# Project_design_v1_0.net
KiCad netlist of a schematic drawn in EAGLE
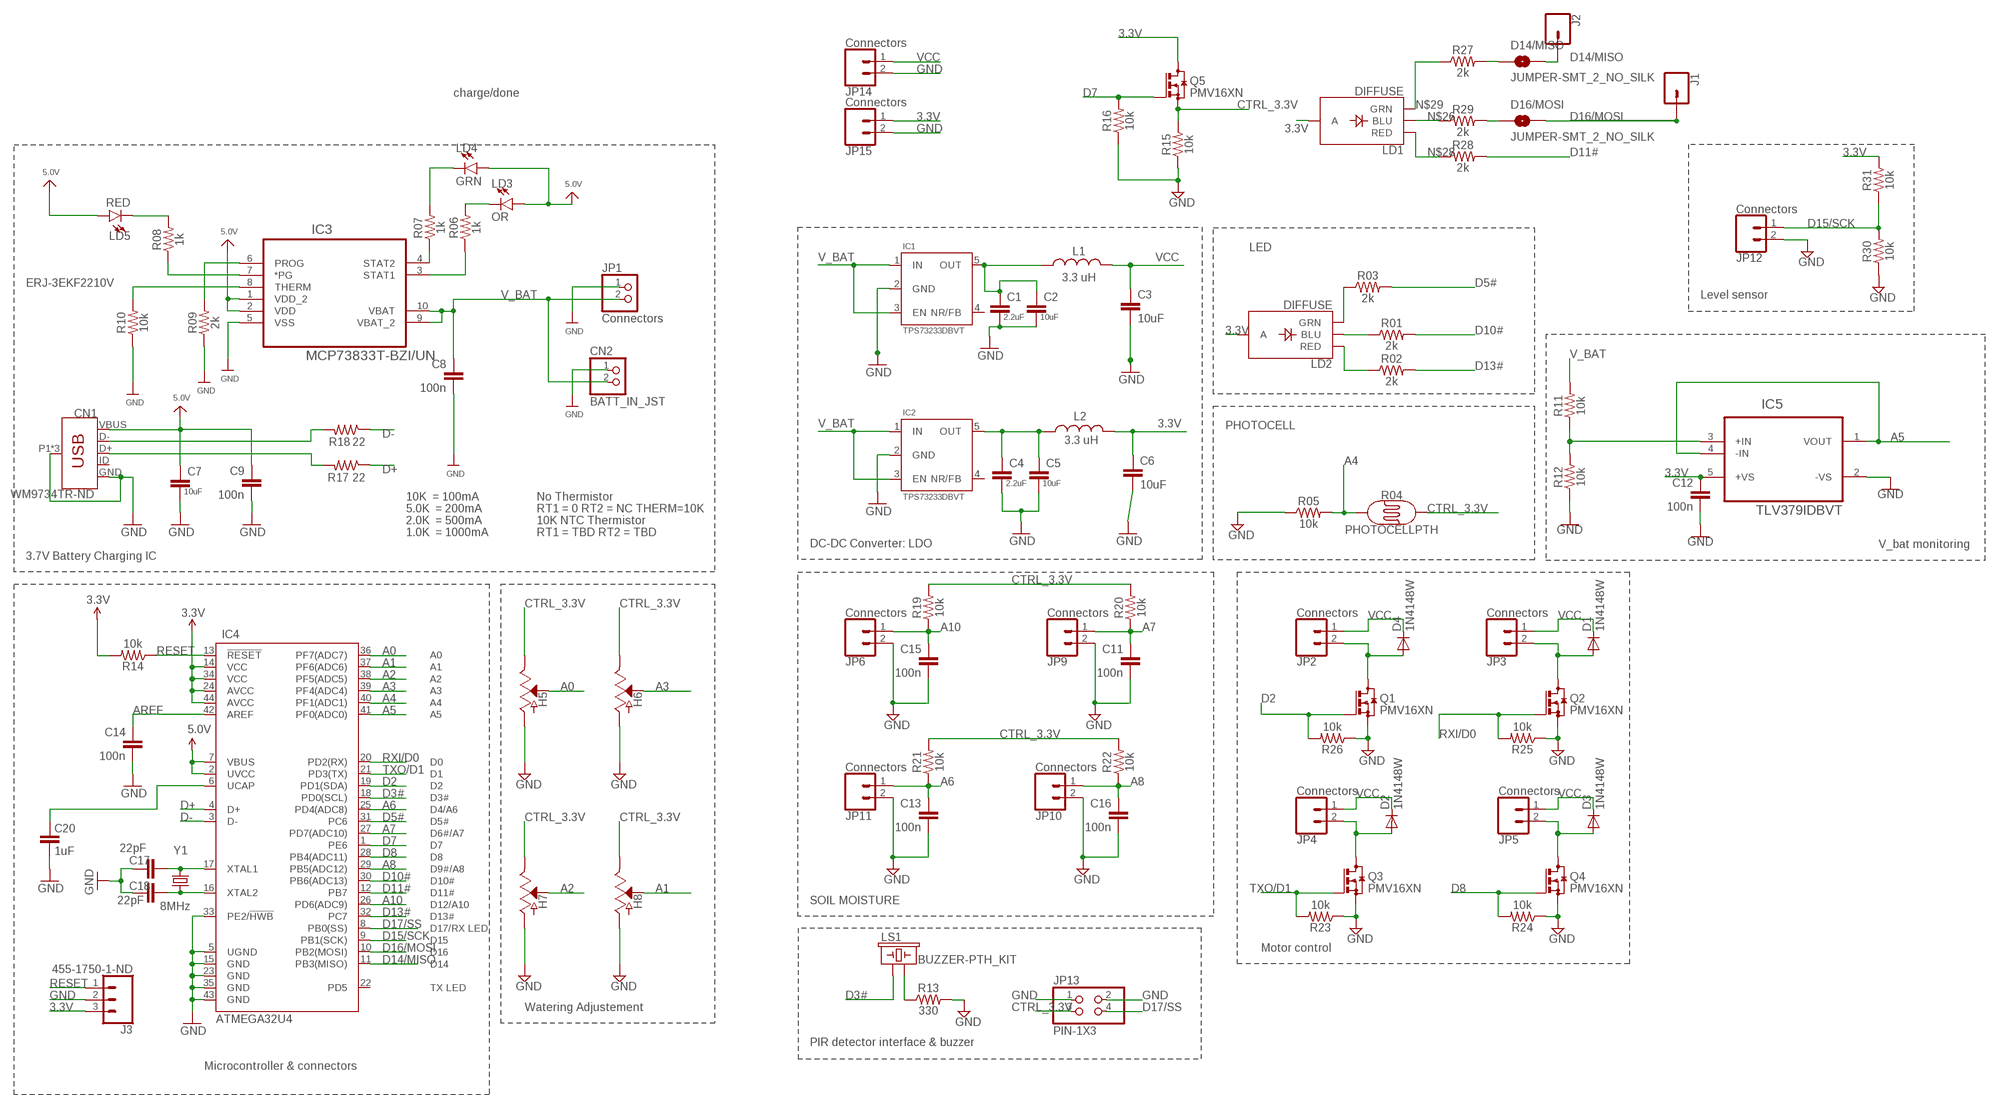
[diagram p0: schematic, sheet 1]

(export (version "E")
  (design (tool "Eeschema 10.0.6"))
  (components
    (comp (ref "C1")
      (value "2.2uF")
      (footprint "eagle-import:0603-CAP")
      (fields (field (name "PARTNO") "C1608X7S1C225K080AC"))
      (libsource (lib "eagle-import") (part "SparkFun-Passives_CAP0603-CAP"))
    )
    (comp (ref "C2")
      (value "10uF")
      (footprint "eagle-import:0603-CAP")
      (fields (field (name "PARTNO") "GRM188R60J106ME47D"))
      (libsource (lib "eagle-import") (part "SparkFun-Passives_CAP0603-CAP"))
    )
    (comp (ref "C3")
      (value "10uF")
      (footprint "eagle-import:0603-CAP")
      (fields (field (name "PARTNO") "GRM188R60J106ME47D"))
      (libsource (lib "eagle-import") (part "SparkFun-Passives_CAP0603-CAP"))
    )
    (comp (ref "C4")
      (value "2.2uF")
      (footprint "eagle-import:0603-CAP")
      (fields (field (name "PARTNO") "C1608X7S1C225K080AC"))
      (libsource (lib "eagle-import") (part "SparkFun-Passives_CAP0603-CAP"))
    )
    (comp (ref "C5")
      (value "10uF")
      (footprint "eagle-import:0603-CAP")
      (fields (field (name "PARTNO") "GRM188R60J106ME47D"))
      (libsource (lib "eagle-import") (part "SparkFun-Passives_CAP0603-CAP"))
    )
    (comp (ref "C6")
      (value "10uF")
      (footprint "eagle-import:0603-CAP")
      (fields (field (name "PARTNO") "GRM188R60J106ME47D"))
      (libsource (lib "eagle-import") (part "SparkFun-Passives_CAP0603-CAP"))
    )
    (comp (ref "C7")
      (value "10uF")
      (footprint "eagle-import:0603-CAP")
      (fields (field (name "PARTNO") "GRM188R60J106ME47D"))
      (libsource (lib "eagle-import") (part "SparkFun-Passives_CAP0603-CAP"))
    )
    (comp (ref "C8")
      (value "100n")
      (footprint "eagle-import:0402")
      (fields (field (name "PARTNO") "CGA2B3X7R1E104K050BB"))
      (libsource (lib "eagle-import") (part "CAPA0402"))
    )
    (comp (ref "C9")
      (value "100n")
      (footprint "eagle-import:0402")
      (fields (field (name "PARTNO") "CGA2B3X7R1E104K050BB"))
      (libsource (lib "eagle-import") (part "CAPA0402"))
    )
    (comp (ref "C11")
      (value "100n")
      (footprint "eagle-import:0402")
      (fields (field (name "PARTNO") "CGA2B3X7R1E104K050BB"))
      (libsource (lib "eagle-import") (part "CAPA0402"))
    )
    (comp (ref "C12")
      (value "100n")
      (footprint "eagle-import:0402")
      (fields (field (name "PARTNO") "CGA2B3X7R1E104K050BB"))
      (libsource (lib "eagle-import") (part "CAPA0402"))
    )
    (comp (ref "C13")
      (value "100n")
      (footprint "eagle-import:0402")
      (fields (field (name "PARTNO") "CGA2B3X7R1E104K050BB"))
      (libsource (lib "eagle-import") (part "CAPA0402"))
    )
    (comp (ref "C14")
      (value "100n")
      (footprint "eagle-import:0402")
      (fields (field (name "PARTNO") "CGA2B3X7R1E104K050BB"))
      (libsource (lib "eagle-import") (part "CAPA0402"))
    )
    (comp (ref "C15")
      (value "100n")
      (footprint "eagle-import:0402")
      (fields (field (name "PARTNO") "CGA2B3X7R1E104K050BB"))
      (libsource (lib "eagle-import") (part "CAPA0402"))
    )
    (comp (ref "C16")
      (value "100n")
      (footprint "eagle-import:0402")
      (fields (field (name "PARTNO") "CGA2B3X7R1E104K050BB"))
      (libsource (lib "eagle-import") (part "CAPA0402"))
    )
    (comp (ref "C17")
      (value "22pF")
      (footprint "eagle-import:0603-CAP")
      (fields (field (name "PARTNO") "CL10C2R2BB8NNNC"))
      (libsource (lib "eagle-import") (part "CAP0603-CAP"))
    )
    (comp (ref "C18")
      (value "22pF")
      (footprint "eagle-import:0603-CAP")
      (fields (field (name "PARTNO") "CL10C2R2BB8NNNC"))
      (libsource (lib "eagle-import") (part "CAP0603-CAP"))
    )
    (comp (ref "C20")
      (value "1uF")
      (footprint "eagle-import:0603-CAP")
      (fields (field (name "PARTNO") "CL10B105KP8NNNC"))
      (libsource (lib "eagle-import") (part "CAP0603-CAP"))
    )
    (comp (ref "CN1")
      (value "WM9734TR-ND")
      (footprint "eagle-import:USB-B-MICRO-SMD_VERT")
      (fields (field (name "PARTNO") "1051330011"))
      (libsource (lib "eagle-import") (part "USB_MICRO-B_FEMALE-SMT-VERT"))
    )
    (comp (ref "CN2")
      (value "BATT_IN_JST")
      (footprint "eagle-import:JSTPH2")
      (fields (field (name "PARTNO") "B2B-XH-A(LF)(SN)"))
      (libsource (lib "eagle-import") (part "JST_2PIN"))
    )
    (comp (ref "D1")
      (value "1N4148W")
      (footprint "eagle-import:SOD-123_MINI-SMA")
      (libsource (lib "eagle-import") (part "CGRM400-G2"))
    )
    (comp (ref "D2")
      (value "1N4148W")
      (footprint "eagle-import:SOD-123_MINI-SMA")
      (libsource (lib "eagle-import") (part "CGRM400-G2"))
    )
    (comp (ref "D3")
      (value "1N4148W")
      (footprint "eagle-import:SOD-123_MINI-SMA")
      (libsource (lib "eagle-import") (part "CGRM400-G2"))
    )
    (comp (ref "D4")
      (value "1N4148W")
      (footprint "eagle-import:SOD-123_MINI-SMA")
      (libsource (lib "eagle-import") (part "CGRM400-G2"))
    )
    (comp (ref "D14/MISO")
      (value "JUMPER-SMT_2_NO_SILK")
      (footprint "eagle-import:SMT-JUMPER_2_NO_SILK")
      (libsource (lib "eagle-import") (part "JUMPER-SMT_2_NO_SILK"))
    )
    (comp (ref "D16/MOSI")
      (value "JUMPER-SMT_2_NO_SILK")
      (footprint "eagle-import:SMT-JUMPER_2_NO_SILK")
      (libsource (lib "eagle-import") (part "JUMPER-SMT_2_NO_SILK"))
    )
    (comp (ref "H5")
      (value "POT1")
      (footprint "eagle-import:SOIL_MOISTURE")
      (fields (field (name "PARTNO") "SEN-13322"))
      (libsource (lib "eagle-import") (part "SOIL_MOISTURE"))
    )
    (comp (ref "H6")
      (value "POT2")
      (footprint "eagle-import:SOIL_MOISTURE")
      (fields (field (name "PARTNO") "SEN-13322"))
      (libsource (lib "eagle-import") (part "SOIL_MOISTURE"))
    )
    (comp (ref "H7")
      (value "POT3")
      (footprint "eagle-import:SOIL_MOISTURE")
      (fields (field (name "PARTNO") "SEN-13322"))
      (libsource (lib "eagle-import") (part "SOIL_MOISTURE"))
    )
    (comp (ref "H8")
      (value "POT4")
      (footprint "eagle-import:SOIL_MOISTURE")
      (fields (field (name "PARTNO") "SEN-13322"))
      (libsource (lib "eagle-import") (part "SOIL_MOISTURE"))
    )
    (comp (ref "IC1")
      (value "TPS73233DBVT")
      (footprint "eagle-import:SOT23-5")
      (libsource (lib "eagle-import") (part "TPS732XXDBV"))
    )
    (comp (ref "IC2")
      (value "TPS73233DBVT")
      (footprint "eagle-import:SOT23-5")
      (libsource (lib "eagle-import") (part "TPS732XXDBV"))
    )
    (comp (ref "IC3")
      (value "MCP73833T-BZI/UN")
      (footprint "eagle-import:SOP50P490X110-10N")
      (fields (field (name "MF") "Microchip"))
      (libsource (lib "eagle-import") (part "MCP73833T-BZI/UN"))
    )
    (comp (ref "IC4")
      (value "ATMEGA32U4")
      (footprint "eagle-import:TQFP44")
      (fields
        (field (name "MF") "Microchip")
        (field (name "MP") "ATMEGA32U4RC-AU")
        (field (name "PARTNO") "ATMEGA32U4RC-MUR")
      )
      (libsource (lib "eagle-import") (part "ATMEGA32U4TQFP-44"))
    )
    (comp (ref "IC5")
      (value "TLV379IDBVT")
      (footprint "eagle-import:SOT95P280X145-5N")
      (fields (field (name "MF") "Analog Devices") (field (name "MP") "AD8009JRTZ-REEL"))
      (libsource (lib "eagle-import") (part "AD8009JRTZ-REEL"))
    )
    (comp (ref "J1")
      (value "CONN_01")
      (footprint "eagle-import:1X01")
      (libsource (lib "eagle-import") (part "CONN_01"))
    )
    (comp (ref "J2")
      (value "CONN_01")
      (footprint "eagle-import:1X01")
      (libsource (lib "eagle-import") (part "CONN_01"))
    )
    (comp (ref "J3")
      (value "455-1750-1-ND")
      (footprint "eagle-import:1X03")
      (libsource (lib "eagle-import") (part "CONN_03"))
    )
    (comp (ref "JP1")
      (value "Connectors")
      (footprint "eagle-import:1X02")
      (fields (field (name "PARTNO") "/"))
      (libsource (lib "eagle-import") (part "PINHD-1X2"))
    )
    (comp (ref "JP2")
      (value "Connectors")
      (footprint "eagle-import:1X02")
      (fields (field (name "PARTNO") "M20-9960245"))
      (libsource (lib "eagle-import") (part "CONN_02"))
    )
    (comp (ref "JP3")
      (value "Connectors")
      (footprint "eagle-import:1X02")
      (fields (field (name "PARTNO") "M20-9960245"))
      (libsource (lib "eagle-import") (part "CONN_02"))
    )
    (comp (ref "JP4")
      (value "Connectors")
      (footprint "eagle-import:1X02")
      (fields (field (name "PARTNO") "M20-9960245"))
      (libsource (lib "eagle-import") (part "CONN_02"))
    )
    (comp (ref "JP5")
      (value "Connectors")
      (footprint "eagle-import:1X02")
      (fields (field (name "PARTNO") "M20-9960245"))
      (libsource (lib "eagle-import") (part "CONN_02"))
    )
    (comp (ref "JP6")
      (value "Connectors")
      (footprint "eagle-import:1X02")
      (fields (field (name "PARTNO") "M20-9960245"))
      (libsource (lib "eagle-import") (part "CONN_02"))
    )
    (comp (ref "JP9")
      (value "Connectors")
      (footprint "eagle-import:1X02")
      (fields (field (name "PARTNO") "M20-9960245"))
      (libsource (lib "eagle-import") (part "CONN_02"))
    )
    (comp (ref "JP10")
      (value "Connectors")
      (footprint "eagle-import:1X02")
      (fields (field (name "PARTNO") "M20-9960245"))
      (libsource (lib "eagle-import") (part "CONN_02"))
    )
    (comp (ref "JP11")
      (value "Connectors")
      (footprint "eagle-import:1X02")
      (fields (field (name "PARTNO") "M20-9960245"))
      (libsource (lib "eagle-import") (part "CONN_02"))
    )
    (comp (ref "JP12")
      (value "Connectors")
      (footprint "eagle-import:1X02")
      (fields (field (name "PARTNO") "M20-9960245"))
      (libsource (lib "eagle-import") (part "CONN_02"))
    )
    (comp (ref "JP13")
      (value "PIN-1X3")
      (footprint "eagle-import:2X02")
      (fields (field (name "PARTNO") "M22-2040805"))
      (libsource (lib "eagle-import") (part "PINHD-2X2"))
    )
    (comp (ref "JP14")
      (value "Connectors")
      (footprint "eagle-import:1X02")
      (fields (field (name "PARTNO") "M20-9960245"))
      (libsource (lib "eagle-import") (part "CONN_02"))
    )
    (comp (ref "JP15")
      (value "Connectors")
      (footprint "eagle-import:1X02")
      (fields (field (name "PARTNO") "M20-9960245"))
      (libsource (lib "eagle-import") (part "CONN_02"))
    )
    (comp (ref "L1")
      (value "3.3 uH")
      (footprint "eagle-import:0603")
      (fields (field (name "PARTNO") "LQM18PN3R3MGHD"))
      (libsource (lib "eagle-import") (part "INDUCTOR0603"))
    )
    (comp (ref "L2")
      (value "3.3 uH")
      (footprint "eagle-import:0603")
      (fields (field (name "PARTNO") "LQM18PN3R3MGHD"))
      (libsource (lib "eagle-import") (part "INDUCTOR0603"))
    )
    (comp (ref "LD1")
      (value "DIFFUSE")
      (footprint "eagle-import:LED-RGB_THRU_5MM")
      (fields (field (name "PARTNO") "WP154A4SEJ3VBDZGW/CA"))
      (libsource (lib "eagle-import") (part "LED_RGB_THRU_CA"))
    )
    (comp (ref "LD2")
      (value "DIFFUSE")
      (footprint "eagle-import:LED-RGB_THRU_5MM")
      (fields (field (name "PARTNO") "WP154A4SEJ3VBDZGW/CA"))
      (libsource (lib "eagle-import") (part "LED_RGB_THRU_CA"))
    )
    (comp (ref "LD3")
      (value "OR")
      (footprint "eagle-import:LED_3MM")
      (fields (field (name "PARTNO") "TLHO4600"))
      (libsource (lib "eagle-import") (part "LED3MM"))
    )
    (comp (ref "LD4")
      (value "GRN")
      (footprint "eagle-import:LED_3MM")
      (fields (field (name "PARTNO") "TLLG4400"))
      (libsource (lib "eagle-import") (part "LED3MM"))
    )
    (comp (ref "LD5")
      (value "RED")
      (footprint "eagle-import:LED_3MM")
      (fields (field (name "PARTNO") "TLHK4600"))
      (libsource (lib "eagle-import") (part "LED3MM"))
    )
    (comp (ref "LS1")
      (value "BUZZER-PTH_KIT")
      (footprint "eagle-import:BUZZER-12MM-KIT")
      (fields (field (name "PARTNO") "CEM-1203(42)"))
      (libsource (lib "eagle-import") (part "BUZZER-PTH_KIT"))
    )
    (comp (ref "Q1")
      (value "PMV16XN")
      (footprint "eagle-import:SOT23")
      (fields (field (name "PARTNO") "PMV16XNR"))
      (libsource (lib "eagle-import") (part "PMV16XN"))
    )
    (comp (ref "Q2")
      (value "PMV16XN")
      (footprint "eagle-import:SOT23")
      (fields (field (name "PARTNO") "PMV16XNR"))
      (libsource (lib "eagle-import") (part "PMV16XN"))
    )
    (comp (ref "Q3")
      (value "PMV16XN")
      (footprint "eagle-import:SOT23")
      (fields (field (name "PARTNO") "PMV16XNR"))
      (libsource (lib "eagle-import") (part "PMV16XN"))
    )
    (comp (ref "Q4")
      (value "PMV16XN")
      (footprint "eagle-import:SOT23")
      (fields (field (name "PARTNO") "PMV16XNR"))
      (libsource (lib "eagle-import") (part "PMV16XN"))
    )
    (comp (ref "Q5")
      (value "PMV16XN")
      (footprint "eagle-import:SOT23")
      (fields (field (name "PARTNO") "PMV16XNR"))
      (libsource (lib "eagle-import") (part "PMV16XN"))
    )
    (comp (ref "R01")
      (value "2k")
      (footprint "eagle-import:0603")
      (fields (field (name "PARTNO") "ERJ-PA3F2001V"))
      (libsource (lib "eagle-import") (part "0603RESIST"))
    )
    (comp (ref "R02")
      (value "2k")
      (footprint "eagle-import:0603")
      (fields (field (name "PARTNO") "ERJ-PA3F2001V"))
      (libsource (lib "eagle-import") (part "0603RESIST"))
    )
    (comp (ref "R03")
      (value "2k")
      (footprint "eagle-import:0603")
      (fields (field (name "PARTNO") "ERJ-PA3F2001V"))
      (libsource (lib "eagle-import") (part "0603RESIST"))
    )
    (comp (ref "R04")
      (value "PHOTOCELLPTH")
      (footprint "eagle-import:PHOTOCELL")
      (fields (field (name "PARTNO") "1528-2141-ND"))
      (libsource (lib "eagle-import") (part "PHOTOCELLPTH"))
    )
    (comp (ref "R05")
      (value "10k")
      (footprint "eagle-import:0603")
      (fields (field (name "PARTNO") "ERA-3AEB103V"))
      (libsource (lib "eagle-import") (part "0603RESIST"))
    )
    (comp (ref "R06")
      (value "1k")
      (footprint "eagle-import:0603")
      (fields (field (name "PARTNO") "RC0603JR-07330RL"))
      (libsource (lib "eagle-import") (part "0603RESIST"))
    )
    (comp (ref "R07")
      (value "1k")
      (footprint "eagle-import:0603")
      (fields (field (name "PARTNO") "RC0603JR-07330RL"))
      (libsource (lib "eagle-import") (part "0603RESIST"))
    )
    (comp (ref "R08")
      (value "1k")
      (footprint "eagle-import:0603")
      (fields (field (name "PARTNO") "RC0603JR-07330RL"))
      (libsource (lib "eagle-import") (part "0603RESIST"))
    )
    (comp (ref "R09")
      (value "2k")
      (footprint "eagle-import:0603")
      (fields (field (name "PARTNO") "ERJ-PA3F2001V"))
      (libsource (lib "eagle-import") (part "0603RESIST"))
    )
    (comp (ref "R10")
      (value "10k")
      (footprint "eagle-import:0603")
      (fields (field (name "PARTNO") "ERA-3AEB103V"))
      (libsource (lib "eagle-import") (part "0603RESIST"))
    )
    (comp (ref "R11")
      (value "10k")
      (footprint "eagle-import:0603")
      (fields (field (name "PARTNO") "ERA-3AEB103V"))
      (libsource (lib "eagle-import") (part "0603RESIST"))
    )
    (comp (ref "R12")
      (value "10k")
      (footprint "eagle-import:0603")
      (fields (field (name "PARTNO") "ERA-3AEB103V"))
      (libsource (lib "eagle-import") (part "0603RESIST"))
    )
    (comp (ref "R13")
      (value "330")
      (footprint "eagle-import:0603")
      (fields (field (name "PARTNO") "RC0603JR-07330RL"))
      (libsource (lib "eagle-import") (part "0603RESIST"))
    )
    (comp (ref "R14")
      (value "10k")
      (footprint "eagle-import:0603")
      (fields (field (name "PARTNO") "ERA-3AEB103V"))
      (libsource (lib "eagle-import") (part "0603RESIST"))
    )
    (comp (ref "R15")
      (value "10k")
      (footprint "eagle-import:0603")
      (fields (field (name "PARTNO") "ERA-3AEB103V"))
      (libsource (lib "eagle-import") (part "0603RESIST"))
    )
    (comp (ref "R16")
      (value "10k")
      (footprint "eagle-import:0603")
      (fields (field (name "PARTNO") "ERA-3AEB103V"))
      (libsource (lib "eagle-import") (part "0603RESIST"))
    )
    (comp (ref "R17")
      (value "22")
      (footprint "eagle-import:0603-RES")
      (fields (field (name "PARTNO") "RC0603JR-0722RL"))
      (libsource (lib "eagle-import") (part "RESISTOR0603-RES"))
    )
    (comp (ref "R18")
      (value "22")
      (footprint "eagle-import:0603-RES")
      (fields (field (name "PARTNO") "RC0603JR-0722RL"))
      (libsource (lib "eagle-import") (part "RESISTOR0603-RES"))
    )
    (comp (ref "R19")
      (value "10k")
      (footprint "eagle-import:0603")
      (fields (field (name "PARTNO") "ERA-3AEB103V"))
      (libsource (lib "eagle-import") (part "0603RESIST"))
    )
    (comp (ref "R20")
      (value "10k")
      (footprint "eagle-import:0603")
      (fields (field (name "PARTNO") "ERA-3AEB103V"))
      (libsource (lib "eagle-import") (part "0603RESIST"))
    )
    (comp (ref "R21")
      (value "10k")
      (footprint "eagle-import:0603")
      (fields (field (name "PARTNO") "ERA-3AEB103V"))
      (libsource (lib "eagle-import") (part "0603RESIST"))
    )
    (comp (ref "R22")
      (value "10k")
      (footprint "eagle-import:0603")
      (fields (field (name "PARTNO") "ERA-3AEB103V"))
      (libsource (lib "eagle-import") (part "0603RESIST"))
    )
    (comp (ref "R23")
      (value "10k")
      (footprint "eagle-import:0603")
      (fields (field (name "PARTNO") "ERA-3AEB103V"))
      (libsource (lib "eagle-import") (part "0603RESIST"))
    )
    (comp (ref "R24")
      (value "10k")
      (footprint "eagle-import:0603")
      (fields (field (name "PARTNO") "ERA-3AEB103V"))
      (libsource (lib "eagle-import") (part "0603RESIST"))
    )
    (comp (ref "R25")
      (value "10k")
      (footprint "eagle-import:0603")
      (fields (field (name "PARTNO") "ERA-3AEB103V"))
      (libsource (lib "eagle-import") (part "0603RESIST"))
    )
    (comp (ref "R26")
      (value "10k")
      (footprint "eagle-import:0603")
      (fields (field (name "PARTNO") "ERA-3AEB103V"))
      (libsource (lib "eagle-import") (part "0603RESIST"))
    )
    (comp (ref "R27")
      (value "2k")
      (footprint "eagle-import:0603")
      (fields (field (name "PARTNO") "ERJ-PA3F2001V"))
      (libsource (lib "eagle-import") (part "0603RESIST"))
    )
    (comp (ref "R28")
      (value "2k")
      (footprint "eagle-import:0603")
      (fields (field (name "PARTNO") "ERJ-PA3F2001V"))
      (libsource (lib "eagle-import") (part "0603RESIST"))
    )
    (comp (ref "R29")
      (value "2k")
      (footprint "eagle-import:0603")
      (fields (field (name "PARTNO") "ERJ-PA3F2001V"))
      (libsource (lib "eagle-import") (part "0603RESIST"))
    )
    (comp (ref "R30")
      (value "10k")
      (footprint "eagle-import:0603")
      (fields (field (name "PARTNO") "ERA-3AEB103V"))
      (libsource (lib "eagle-import") (part "0603RESIST"))
    )
    (comp (ref "R31")
      (value "10k")
      (footprint "eagle-import:0603")
      (fields (field (name "PARTNO") "ERA-3AEB103V"))
      (libsource (lib "eagle-import") (part "0603RESIST"))
    )
    (comp (ref "Y1")
      (value "8MHz")
      (footprint "eagle-import:CRYSTAL-SMD-5X3")
      (fields (field (name "PARTNO") "ABM3C-8.000MHZ-D4Y-T"))
      (libsource (lib "eagle-import") (part "CRYSTAL5X3"))
    )
  )
  (nets
    (net (code "1") (name "/A0") (class "Default")
      (node (ref "H5") (pin "3") (pinfunction "VOUT_3") (pintype "passive"))
      (node (ref "IC4") (pin "36") (pinfunction "PF7(ADC7)_36") (pintype "bidirectional"))
    )
    (net (code "2") (name "/A1") (class "Default")
      (node (ref "H8") (pin "3") (pinfunction "VOUT_3") (pintype "passive"))
      (node (ref "IC4") (pin "37") (pinfunction "PF6(ADC6)_37") (pintype "bidirectional"))
    )
    (net (code "3") (name "/A2") (class "Default")
      (node (ref "H7") (pin "3") (pinfunction "VOUT_3") (pintype "passive"))
      (node (ref "IC4") (pin "38") (pinfunction "PF5(ADC5)_38") (pintype "bidirectional"))
    )
    (net (code "4") (name "/A3") (class "Default")
      (node (ref "H6") (pin "3") (pinfunction "VOUT_3") (pintype "passive"))
      (node (ref "IC4") (pin "39") (pinfunction "PF4(ADC4)_39") (pintype "bidirectional"))
    )
    (net (code "5") (name "/A4") (class "Default")
      (node (ref "IC4") (pin "40") (pinfunction "PF1(ADC1)_40") (pintype "bidirectional"))
      (node (ref "R04") (pin "1") (pinfunction "P$1_1") (pintype "bidirectional"))
      (node (ref "R05") (pin "2") (pinfunction "2_2") (pintype "passive"))
    )
    (net (code "6") (name "/A5") (class "Default")
      (node (ref "IC4") (pin "41") (pinfunction "PF0(ADC0)_41") (pintype "bidirectional"))
      (node (ref "IC5") (pin "1") (pinfunction "VOUT_1") (pintype "passive"))
      (node (ref "IC5") (pin "4") (pinfunction "-IN_4") (pintype "passive"))
    )
    (net (code "7") (name "/A6") (class "Default")
      (node (ref "C13") (pin "1") (pinfunction "1_1") (pintype "passive"))
      (node (ref "IC4") (pin "25") (pinfunction "PD4(ADC8)_25") (pintype "bidirectional"))
      (node (ref "JP11") (pin "1") (pinfunction "1_1") (pintype "passive"))
      (node (ref "R21") (pin "1") (pinfunction "1_1") (pintype "passive"))
    )
    (net (code "8") (name "/A7") (class "Default")
      (node (ref "C11") (pin "1") (pinfunction "1_1") (pintype "passive"))
      (node (ref "IC4") (pin "27") (pinfunction "PD7(ADC10)_27") (pintype "bidirectional"))
      (node (ref "JP9") (pin "1") (pinfunction "1_1") (pintype "passive"))
      (node (ref "R20") (pin "1") (pinfunction "1_1") (pintype "passive"))
    )
    (net (code "9") (name "/A8") (class "Default")
      (node (ref "C16") (pin "1") (pinfunction "1_1") (pintype "passive"))
      (node (ref "IC4") (pin "29") (pinfunction "PB5(ADC12)_29") (pintype "bidirectional"))
      (node (ref "JP10") (pin "1") (pinfunction "1_1") (pintype "passive"))
      (node (ref "R22") (pin "1") (pinfunction "1_1") (pintype "passive"))
    )
    (net (code "10") (name "/A10") (class "Default")
      (node (ref "C15") (pin "1") (pinfunction "1_1") (pintype "passive"))
      (node (ref "IC4") (pin "26") (pinfunction "PD6(ADC9)_26") (pintype "bidirectional"))
      (node (ref "JP6") (pin "1") (pinfunction "1_1") (pintype "passive"))
      (node (ref "R19") (pin "1") (pinfunction "1_1") (pintype "passive"))
    )
    (net (code "11") (name "/AREF") (class "Default")
      (node (ref "C14") (pin "1") (pinfunction "1_1") (pintype "passive"))
      (node (ref "IC4") (pin "42") (pinfunction "AREF_42") (pintype "bidirectional"))
    )
    (net (code "12") (name "/CTRL_3.3V") (class "Default")
      (node (ref "H5") (pin "1") (pinfunction "VCC_1") (pintype "passive"))
      (node (ref "H6") (pin "1") (pinfunction "VCC_1") (pintype "passive"))
      (node (ref "H7") (pin "1") (pinfunction "VCC_1") (pintype "passive"))
      (node (ref "H8") (pin "1") (pinfunction "VCC_1") (pintype "passive"))
      (node (ref "JP13") (pin "3") (pinfunction "3_3") (pintype "passive"))
      (node (ref "Q5") (pin "2") (pinfunction "S_2") (pintype "passive"))
      (node (ref "R04") (pin "2") (pinfunction "P$2_2") (pintype "bidirectional"))
      (node (ref "R15") (pin "2") (pinfunction "2_2") (pintype "passive"))
      (node (ref "R19") (pin "2") (pinfunction "2_2") (pintype "passive"))
      (node (ref "R20") (pin "2") (pinfunction "2_2") (pintype "passive"))
      (node (ref "R21") (pin "2") (pinfunction "2_2") (pintype "passive"))
      (node (ref "R22") (pin "2") (pinfunction "2_2") (pintype "passive"))
    )
    (net (code "13") (name "/D+") (class "Default")
      (node (ref "IC4") (pin "4") (pinfunction "D+_4") (pintype "bidirectional"))
      (node (ref "R17") (pin "1") (pinfunction "1_1") (pintype "passive"))
    )
    (net (code "14") (name "/D-") (class "Default")
      (node (ref "IC4") (pin "3") (pinfunction "D-_3") (pintype "bidirectional"))
      (node (ref "R18") (pin "1") (pinfunction "1_1") (pintype "passive"))
    )
    (net (code "15") (name "/D2") (class "Default")
      (node (ref "IC4") (pin "19") (pinfunction "PD1(SDA)_19") (pintype "bidirectional"))
      (node (ref "Q1") (pin "1") (pinfunction "G_1") (pintype "passive"))
      (node (ref "R26") (pin "2") (pinfunction "2_2") (pintype "passive"))
    )
    (net (code "16") (name "/D3#") (class "Default")
      (node (ref "IC4") (pin "18") (pinfunction "PD0(SCL)_18") (pintype "bidirectional"))
      (node (ref "LS1") (pin "+") (pinfunction "1_+") (pintype "passive"))
    )
    (net (code "17") (name "/D5#") (class "Default")
      (node (ref "IC4") (pin "31") (pinfunction "PC6_31") (pintype "bidirectional"))
      (node (ref "R03") (pin "2") (pinfunction "2_2") (pintype "passive"))
    )
    (net (code "18") (name "/D7") (class "Default")
      (node (ref "IC4") (pin "1") (pinfunction "PE6_1") (pintype "bidirectional"))
      (node (ref "Q5") (pin "1") (pinfunction "G_1") (pintype "passive"))
      (node (ref "R16") (pin "2") (pinfunction "2_2") (pintype "passive"))
    )
    (net (code "19") (name "/D8") (class "Default")
      (node (ref "IC4") (pin "28") (pinfunction "PB4(ADC11)_28") (pintype "bidirectional"))
      (node (ref "Q4") (pin "1") (pinfunction "G_1") (pintype "passive"))
      (node (ref "R24") (pin "2") (pinfunction "2_2") (pintype "passive"))
    )
    (net (code "20") (name "/D10#") (class "Default")
      (node (ref "IC4") (pin "30") (pinfunction "PB6(ADC13)_30") (pintype "bidirectional"))
      (node (ref "R01") (pin "2") (pinfunction "2_2") (pintype "passive"))
    )
    (net (code "21") (name "/D11#") (class "Default")
      (node (ref "IC4") (pin "12") (pinfunction "PB7_12") (pintype "bidirectional"))
      (node (ref "R28") (pin "2") (pinfunction "2_2") (pintype "passive"))
    )
    (net (code "22") (name "/D13#") (class "Default")
      (node (ref "IC4") (pin "32") (pinfunction "PC7_32") (pintype "bidirectional"))
      (node (ref "R02") (pin "2") (pinfunction "2_2") (pintype "passive"))
    )
    (net (code "23") (name "/D14{slash}MISO") (class "Default")
      (node (ref "D14/MISO") (pin "2") (pinfunction "2_2") (pintype "passive"))
      (node (ref "IC4") (pin "11") (pinfunction "PB3(MISO)_11") (pintype "bidirectional"))
      (node (ref "J2") (pin "1") (pinfunction "1_1") (pintype "passive"))
    )
    (net (code "24") (name "/D15{slash}SCK") (class "Default")
      (node (ref "IC4") (pin "9") (pinfunction "PB1(SCK)_9") (pintype "bidirectional"))
      (node (ref "JP12") (pin "1") (pinfunction "1_1") (pintype "passive"))
      (node (ref "R30") (pin "2") (pinfunction "2_2") (pintype "passive"))
      (node (ref "R31") (pin "1") (pinfunction "1_1") (pintype "passive"))
    )
    (net (code "25") (name "/D16{slash}MOSI") (class "Default")
      (node (ref "D16/MOSI") (pin "2") (pinfunction "2_2") (pintype "passive"))
      (node (ref "IC4") (pin "10") (pinfunction "PB2(MOSI)_10") (pintype "bidirectional"))
      (node (ref "J1") (pin "1") (pinfunction "1_1") (pintype "passive"))
    )
    (net (code "26") (name "/D17{slash}SS") (class "Default")
      (node (ref "IC4") (pin "8") (pinfunction "PB0(SS)_8") (pintype "bidirectional"))
      (node (ref "JP13") (pin "4") (pinfunction "4_4") (pintype "passive"))
    )
    (net (code "27") (name "/N$26") (class "Default")
      (node (ref "LD1") (pin "1") (pinfunction "BLU_1") (pintype "bidirectional"))
      (node (ref "R29") (pin "1") (pinfunction "1_1") (pintype "passive"))
    )
    (net (code "28") (name "/N$28") (class "Default")
      (node (ref "LD1") (pin "4") (pinfunction "RED_4") (pintype "bidirectional"))
      (node (ref "R28") (pin "1") (pinfunction "1_1") (pintype "passive"))
    )
    (net (code "29") (name "/N$29") (class "Default")
      (node (ref "LD1") (pin "2") (pinfunction "GRN_2") (pintype "bidirectional"))
      (node (ref "R27") (pin "1") (pinfunction "1_1") (pintype "passive"))
    )
    (net (code "30") (name "/RESET") (class "Default")
      (node (ref "IC4") (pin "13") (pinfunction "~{RESET}_13") (pintype "bidirectional"))
      (node (ref "J3") (pin "1") (pinfunction "1_1") (pintype "passive"))
      (node (ref "R14") (pin "1") (pinfunction "1_1") (pintype "passive"))
    )
    (net (code "31") (name "/RXI{slash}D0") (class "Default")
      (node (ref "IC4") (pin "20") (pinfunction "PD2(RX)_20") (pintype "bidirectional"))
      (node (ref "Q2") (pin "1") (pinfunction "G_1") (pintype "passive"))
      (node (ref "R25") (pin "2") (pinfunction "2_2") (pintype "passive"))
    )
    (net (code "32") (name "/TXO{slash}D1") (class "Default")
      (node (ref "IC4") (pin "21") (pinfunction "PD3(TX)_21") (pintype "bidirectional"))
      (node (ref "Q3") (pin "1") (pinfunction "G_1") (pintype "passive"))
      (node (ref "R23") (pin "2") (pinfunction "2_2") (pintype "passive"))
    )
    (net (code "33") (name "/VCC") (class "Default")
      (node (ref "C3") (pin "1") (pinfunction "1_1") (pintype "passive"))
      (node (ref "D1") (pin "C") (pinfunction "C_C") (pintype "passive"))
      (node (ref "D2") (pin "C") (pinfunction "C_C") (pintype "passive"))
      (node (ref "D3") (pin "C") (pinfunction "C_C") (pintype "passive"))
      (node (ref "D4") (pin "C") (pinfunction "C_C") (pintype "passive"))
      (node (ref "JP14") (pin "1") (pinfunction "1_1") (pintype "passive"))
      (node (ref "JP2") (pin "1") (pinfunction "1_1") (pintype "passive"))
      (node (ref "JP3") (pin "1") (pinfunction "1_1") (pintype "passive"))
      (node (ref "JP4") (pin "1") (pinfunction "1_1") (pintype "passive"))
      (node (ref "JP5") (pin "1") (pinfunction "1_1") (pintype "passive"))
      (node (ref "L1") (pin "2") (pinfunction "2_2") (pintype "passive"))
    )
    (net (code "34") (name "/V_BAT") (class "Default")
      (node (ref "C8") (pin "1") (pinfunction "1_1") (pintype "passive"))
      (node (ref "CN2") (pin "2") (pinfunction "2_2") (pintype "passive"))
      (node (ref "IC1") (pin "1") (pinfunction "IN_1") (pintype "bidirectional"))
      (node (ref "IC1") (pin "3") (pinfunction "EN_3") (pintype "bidirectional"))
      (node (ref "IC2") (pin "1") (pinfunction "IN_1") (pintype "bidirectional"))
      (node (ref "IC2") (pin "3") (pinfunction "EN_3") (pintype "bidirectional"))
      (node (ref "IC3") (pin "10") (pinfunction "VBAT_10") (pintype "output"))
      (node (ref "IC3") (pin "9") (pinfunction "VBAT_2_9") (pintype "output"))
      (node (ref "JP1") (pin "2") (pinfunction "2_2") (pintype "passive"))
      (node (ref "R11") (pin "2") (pinfunction "2_2") (pintype "passive"))
    )
    (net (code "35") (name "3.3V") (class "Default")
      (node (ref "C12") (pin "1") (pinfunction "1_1") (pintype "passive"))
      (node (ref "C6") (pin "1") (pinfunction "1_1") (pintype "passive"))
      (node (ref "IC4") (pin "14") (pinfunction "VCC_14") (pintype "bidirectional"))
      (node (ref "IC4") (pin "24") (pinfunction "AVCC_24") (pintype "bidirectional"))
      (node (ref "IC4") (pin "34") (pinfunction "VCC_34") (pintype "bidirectional"))
      (node (ref "IC4") (pin "44") (pinfunction "AVCC_44") (pintype "bidirectional"))
      (node (ref "IC5") (pin "5") (pinfunction "+VS_5") (pintype "power_in"))
      (node (ref "J3") (pin "3") (pinfunction "3_3") (pintype "passive"))
      (node (ref "JP15") (pin "1") (pinfunction "1_1") (pintype "passive"))
      (node (ref "L2") (pin "2") (pinfunction "2_2") (pintype "passive"))
      (node (ref "LD1") (pin "3") (pinfunction "A_3") (pintype "bidirectional"))
      (node (ref "LD2") (pin "3") (pinfunction "A_3") (pintype "bidirectional"))
      (node (ref "Q5") (pin "3") (pinfunction "D_3") (pintype "passive"))
      (node (ref "R14") (pin "2") (pinfunction "2_2") (pintype "passive"))
      (node (ref "R31") (pin "2") (pinfunction "2_2") (pintype "passive"))
    )
    (net (code "36") (name "5.0V") (class "Default")
      (node (ref "C7") (pin "1") (pinfunction "1_1") (pintype "passive"))
      (node (ref "C9") (pin "1") (pinfunction "1_1") (pintype "passive"))
      (node (ref "CN1") (pin "VBUS") (pinfunction "VBUS_VBUS") (pintype "power_in"))
      (node (ref "IC3") (pin "1") (pinfunction "VDD_2_1") (pintype "power_in"))
      (node (ref "IC3") (pin "2") (pinfunction "VDD_2") (pintype "power_in"))
      (node (ref "IC4") (pin "2") (pinfunction "UVCC_2") (pintype "bidirectional"))
      (node (ref "IC4") (pin "7") (pinfunction "VBUS_7") (pintype "bidirectional"))
      (node (ref "LD3") (pin "A") (pinfunction "A_A") (pintype "passive"))
      (node (ref "LD4") (pin "A") (pinfunction "A_A") (pintype "passive"))
      (node (ref "LD5") (pin "A") (pinfunction "A_A") (pintype "passive"))
    )
    (net (code "37") (name "GND") (class "Default")
      (node (ref "C1") (pin "2") (pinfunction "2_2") (pintype "passive"))
      (node (ref "C11") (pin "2") (pinfunction "2_2") (pintype "passive"))
      (node (ref "C12") (pin "2") (pinfunction "2_2") (pintype "passive"))
      (node (ref "C13") (pin "2") (pinfunction "2_2") (pintype "passive"))
      (node (ref "C14") (pin "2") (pinfunction "2_2") (pintype "passive"))
      (node (ref "C15") (pin "2") (pinfunction "2_2") (pintype "passive"))
      (node (ref "C16") (pin "2") (pinfunction "2_2") (pintype "passive"))
      (node (ref "C17") (pin "2") (pinfunction "2_2") (pintype "passive"))
      (node (ref "C18") (pin "2") (pinfunction "2_2") (pintype "passive"))
      (node (ref "C2") (pin "2") (pinfunction "2_2") (pintype "passive"))
      (node (ref "C20") (pin "1") (pinfunction "1_1") (pintype "passive"))
      (node (ref "C3") (pin "2") (pinfunction "2_2") (pintype "passive"))
      (node (ref "C4") (pin "2") (pinfunction "2_2") (pintype "passive"))
      (node (ref "C5") (pin "2") (pinfunction "2_2") (pintype "passive"))
      (node (ref "C6") (pin "2") (pinfunction "2_2") (pintype "passive"))
      (node (ref "C7") (pin "2") (pinfunction "2_2") (pintype "passive"))
      (node (ref "C8") (pin "2") (pinfunction "2_2") (pintype "passive"))
      (node (ref "C9") (pin "2") (pinfunction "2_2") (pintype "passive"))
      (node (ref "CN1") (pin "GND") (pinfunction "GND_GND") (pintype "power_in"))
      (node (ref "CN1") (pin "P1") (pinfunction "SHIELD_P1") (pintype "bidirectional"))
      (node (ref "CN1") (pin "P2") (pinfunction "SHIELD_P2") (pintype "bidirectional"))
      (node (ref "CN1") (pin "P3") (pinfunction "SHIELD_P3") (pintype "bidirectional"))
      (node (ref "CN2") (pin "1") (pinfunction "1_1") (pintype "passive"))
      (node (ref "H5") (pin "2") (pinfunction "GND_2") (pintype "passive"))
      (node (ref "H6") (pin "2") (pinfunction "GND_2") (pintype "passive"))
      (node (ref "H7") (pin "2") (pinfunction "GND_2") (pintype "passive"))
      (node (ref "H8") (pin "2") (pinfunction "GND_2") (pintype "passive"))
      (node (ref "IC1") (pin "2") (pinfunction "GND_2") (pintype "bidirectional"))
      (node (ref "IC2") (pin "2") (pinfunction "GND_2") (pintype "bidirectional"))
      (node (ref "IC3") (pin "5") (pinfunction "VSS_5") (pintype "passive"))
      (node (ref "IC4") (pin "15") (pinfunction "GND_15") (pintype "bidirectional"))
      (node (ref "IC4") (pin "23") (pinfunction "GND_23") (pintype "bidirectional"))
      (node (ref "IC4") (pin "33") (pinfunction "PE2/~{HWB}_33") (pintype "bidirectional"))
      (node (ref "IC4") (pin "35") (pinfunction "GND_35") (pintype "bidirectional"))
      (node (ref "IC4") (pin "43") (pinfunction "GND_43") (pintype "bidirectional"))
      (node (ref "IC4") (pin "5") (pinfunction "UGND_5") (pintype "bidirectional"))
      (node (ref "IC5") (pin "2") (pinfunction "-VS_2") (pintype "power_in"))
      (node (ref "J3") (pin "2") (pinfunction "2_2") (pintype "passive"))
      (node (ref "JP1") (pin "1") (pinfunction "1_1") (pintype "passive"))
      (node (ref "JP10") (pin "2") (pinfunction "2_2") (pintype "passive"))
      (node (ref "JP11") (pin "2") (pinfunction "2_2") (pintype "passive"))
      (node (ref "JP12") (pin "2") (pinfunction "2_2") (pintype "passive"))
      (node (ref "JP13") (pin "1") (pinfunction "1_1") (pintype "passive"))
      (node (ref "JP13") (pin "2") (pinfunction "2_2") (pintype "passive"))
      (node (ref "JP14") (pin "2") (pinfunction "2_2") (pintype "passive"))
      (node (ref "JP15") (pin "2") (pinfunction "2_2") (pintype "passive"))
      (node (ref "JP6") (pin "2") (pinfunction "2_2") (pintype "passive"))
      (node (ref "JP9") (pin "2") (pinfunction "2_2") (pintype "passive"))
      (node (ref "Q1") (pin "2") (pinfunction "S_2") (pintype "passive"))
      (node (ref "Q2") (pin "2") (pinfunction "S_2") (pintype "passive"))
      (node (ref "Q3") (pin "2") (pinfunction "S_2") (pintype "passive"))
      (node (ref "Q4") (pin "2") (pinfunction "S_2") (pintype "passive"))
      (node (ref "R05") (pin "1") (pinfunction "1_1") (pintype "passive"))
      (node (ref "R09") (pin "1") (pinfunction "1_1") (pintype "passive"))
      (node (ref "R10") (pin "1") (pinfunction "1_1") (pintype "passive"))
      (node (ref "R12") (pin "1") (pinfunction "1_1") (pintype "passive"))
      (node (ref "R13") (pin "2") (pinfunction "2_2") (pintype "passive"))
      (node (ref "R15") (pin "1") (pinfunction "1_1") (pintype "passive"))
      (node (ref "R16") (pin "1") (pinfunction "1_1") (pintype "passive"))
      (node (ref "R23") (pin "1") (pinfunction "1_1") (pintype "passive"))
      (node (ref "R24") (pin "1") (pinfunction "1_1") (pintype "passive"))
      (node (ref "R25") (pin "1") (pinfunction "1_1") (pintype "passive"))
      (node (ref "R26") (pin "1") (pinfunction "1_1") (pintype "passive"))
      (node (ref "R30") (pin "1") (pinfunction "1_1") (pintype "passive"))
    )
    (net (code "38") (name "Net-(CN1-PadD+)") (class "Default")
      (node (ref "CN1") (pin "D+") (pinfunction "D+_D+") (pintype "bidirectional"))
      (node (ref "R17") (pin "2") (pinfunction "2_2") (pintype "passive"))
    )
    (net (code "39") (name "Net-(CN1-PadD-)") (class "Default")
      (node (ref "CN1") (pin "D-") (pinfunction "D-_D-") (pintype "bidirectional"))
      (node (ref "R18") (pin "2") (pinfunction "2_2") (pintype "passive"))
    )
    (net (code "40") (name "Net-(D14/MISO-Pad1)") (class "Default")
      (node (ref "D14/MISO") (pin "1") (pinfunction "1_1") (pintype "passive"))
      (node (ref "R27") (pin "2") (pinfunction "2_2") (pintype "passive"))
    )
    (net (code "41") (name "Net-(D16/MOSI-Pad1)") (class "Default")
      (node (ref "D16/MOSI") (pin "1") (pinfunction "1_1") (pintype "passive"))
      (node (ref "R29") (pin "2") (pinfunction "2_2") (pintype "passive"))
    )
    (net (code "42") (name "Net-(IC1-OUT)") (class "Default")
      (node (ref "C1") (pin "1") (pinfunction "1_1") (pintype "passive"))
      (node (ref "C2") (pin "1") (pinfunction "1_1") (pintype "passive"))
      (node (ref "IC1") (pin "5") (pinfunction "OUT_5") (pintype "bidirectional"))
      (node (ref "L1") (pin "1") (pinfunction "1_1") (pintype "passive"))
    )
    (net (code "43") (name "Net-(IC2-OUT)") (class "Default")
      (node (ref "C4") (pin "1") (pinfunction "1_1") (pintype "passive"))
      (node (ref "C5") (pin "1") (pinfunction "1_1") (pintype "passive"))
      (node (ref "IC2") (pin "5") (pinfunction "OUT_5") (pintype "bidirectional"))
      (node (ref "L2") (pin "1") (pinfunction "1_1") (pintype "passive"))
    )
    (net (code "44") (name "Net-(IC3-*PG)") (class "Default")
      (node (ref "IC3") (pin "7") (pinfunction "*PG_7") (pintype "input"))
      (node (ref "R08") (pin "1") (pinfunction "1_1") (pintype "passive"))
    )
    (net (code "45") (name "Net-(IC3-PROG)") (class "Default")
      (node (ref "IC3") (pin "6") (pinfunction "PROG_6") (pintype "input"))
      (node (ref "R09") (pin "2") (pinfunction "2_2") (pintype "passive"))
    )
    (net (code "46") (name "Net-(IC3-STAT1)") (class "Default")
      (node (ref "IC3") (pin "3") (pinfunction "STAT1_3") (pintype "output"))
      (node (ref "R06") (pin "1") (pinfunction "1_1") (pintype "passive"))
    )
    (net (code "47") (name "Net-(IC3-STAT2)") (class "Default")
      (node (ref "IC3") (pin "4") (pinfunction "STAT2_4") (pintype "output"))
      (node (ref "R07") (pin "1") (pinfunction "1_1") (pintype "passive"))
    )
    (net (code "48") (name "Net-(IC3-THERM)") (class "Default")
      (node (ref "IC3") (pin "8") (pinfunction "THERM_8") (pintype "input"))
      (node (ref "R10") (pin "2") (pinfunction "2_2") (pintype "passive"))
    )
    (net (code "49") (name "Net-(IC4-UCAP)") (class "Default")
      (node (ref "C20") (pin "2") (pinfunction "2_2") (pintype "passive"))
      (node (ref "IC4") (pin "6") (pinfunction "UCAP_6") (pintype "bidirectional"))
    )
    (net (code "50") (name "Net-(IC4-XTAL1)") (class "Default")
      (node (ref "C17") (pin "1") (pinfunction "1_1") (pintype "passive"))
      (node (ref "IC4") (pin "17") (pinfunction "XTAL1_17") (pintype "bidirectional"))
      (node (ref "Y1") (pin "3") (pinfunction "2_3") (pintype "passive"))
    )
    (net (code "51") (name "Net-(IC4-XTAL2)") (class "Default")
      (node (ref "C18") (pin "1") (pinfunction "1_1") (pintype "passive"))
      (node (ref "IC4") (pin "16") (pinfunction "XTAL2_16") (pintype "bidirectional"))
      (node (ref "Y1") (pin "1") (pinfunction "1_1") (pintype "passive"))
    )
    (net (code "52") (name "Net-(IC5-+IN)") (class "Default")
      (node (ref "IC5") (pin "3") (pinfunction "+IN_3") (pintype "passive"))
      (node (ref "R11") (pin "1") (pinfunction "1_1") (pintype "passive"))
      (node (ref "R12") (pin "2") (pinfunction "2_2") (pintype "passive"))
    )
    (net (code "53") (name "Net-(LD2-BLU)") (class "Default")
      (node (ref "LD2") (pin "1") (pinfunction "BLU_1") (pintype "bidirectional"))
      (node (ref "R01") (pin "1") (pinfunction "1_1") (pintype "passive"))
    )
    (net (code "54") (name "Net-(LD2-GRN)") (class "Default")
      (node (ref "LD2") (pin "2") (pinfunction "GRN_2") (pintype "bidirectional"))
      (node (ref "R03") (pin "1") (pinfunction "1_1") (pintype "passive"))
    )
    (net (code "55") (name "Net-(LD2-RED)") (class "Default")
      (node (ref "LD2") (pin "4") (pinfunction "RED_4") (pintype "bidirectional"))
      (node (ref "R02") (pin "1") (pinfunction "1_1") (pintype "passive"))
    )
    (net (code "56") (name "Net-(LD3-C)") (class "Default")
      (node (ref "LD3") (pin "K") (pinfunction "C_K") (pintype "passive"))
      (node (ref "R06") (pin "2") (pinfunction "2_2") (pintype "passive"))
    )
    (net (code "57") (name "Net-(LD4-C)") (class "Default")
      (node (ref "LD4") (pin "K") (pinfunction "C_K") (pintype "passive"))
      (node (ref "R07") (pin "2") (pinfunction "2_2") (pintype "passive"))
    )
    (net (code "58") (name "Net-(LD5-C)") (class "Default")
      (node (ref "LD5") (pin "K") (pinfunction "C_K") (pintype "passive"))
      (node (ref "R08") (pin "2") (pinfunction "2_2") (pintype "passive"))
    )
    (net (code "59") (name "Net-(LS1-2)") (class "Default")
      (node (ref "LS1") (pin "-") (pinfunction "2_-") (pintype "passive"))
      (node (ref "R13") (pin "1") (pinfunction "1_1") (pintype "passive"))
    )
    (net (code "60") (name "Net-(Q1-D)") (class "Default")
      (node (ref "D4") (pin "A") (pinfunction "A_A") (pintype "passive"))
      (node (ref "JP2") (pin "2") (pinfunction "2_2") (pintype "passive"))
      (node (ref "Q1") (pin "3") (pinfunction "D_3") (pintype "passive"))
    )
    (net (code "61") (name "Net-(Q2-D)") (class "Default")
      (node (ref "D1") (pin "A") (pinfunction "A_A") (pintype "passive"))
      (node (ref "JP3") (pin "2") (pinfunction "2_2") (pintype "passive"))
      (node (ref "Q2") (pin "3") (pinfunction "D_3") (pintype "passive"))
    )
    (net (code "62") (name "Net-(Q3-D)") (class "Default")
      (node (ref "D2") (pin "A") (pinfunction "A_A") (pintype "passive"))
      (node (ref "JP4") (pin "2") (pinfunction "2_2") (pintype "passive"))
      (node (ref "Q3") (pin "3") (pinfunction "D_3") (pintype "passive"))
    )
    (net (code "63") (name "Net-(Q4-D)") (class "Default")
      (node (ref "D3") (pin "A") (pinfunction "A_A") (pintype "passive"))
      (node (ref "JP5") (pin "2") (pinfunction "2_2") (pintype "passive"))
      (node (ref "Q4") (pin "3") (pinfunction "D_3") (pintype "passive"))
    )
    (net (code "64") (name "unconnected-(CN1-PadID)") (class "Default")
      (node (ref "CN1") (pin "ID") (pinfunction "ID_ID") (pintype "bidirectional"))
    )
    (net (code "65") (name "unconnected-(IC1-NR{slash}FB-Pad4)") (class "Default")
      (node (ref "IC1") (pin "4") (pinfunction "NR/FB_4") (pintype "bidirectional"))
    )
    (net (code "66") (name "unconnected-(IC2-NR{slash}FB-Pad4)") (class "Default")
      (node (ref "IC2") (pin "4") (pinfunction "NR/FB_4") (pintype "bidirectional"))
    )
    (net (code "67") (name "unconnected-(IC4-PD5-Pad22)") (class "Default")
      (node (ref "IC4") (pin "22") (pinfunction "PD5_22") (pintype "bidirectional"))
    )
  )
)
